# arduino.net
KiCad netlist of a schematic drawn in EAGLE
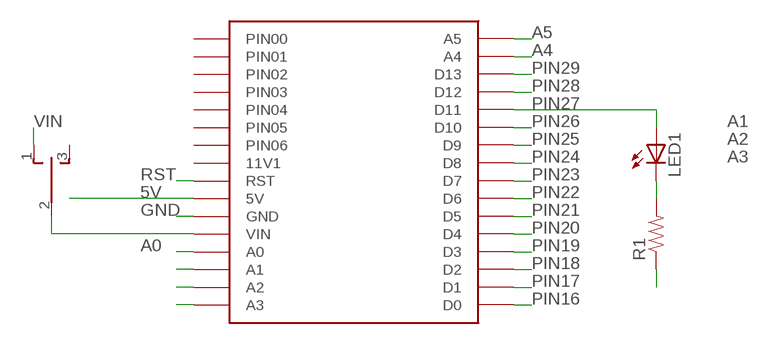
[diagram p0: schematic, sheet 1]
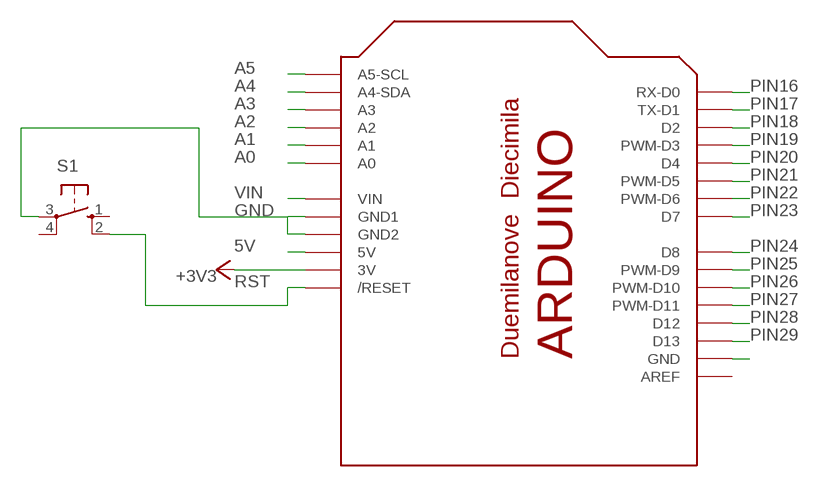
[diagram p1: schematic, sheet 2]
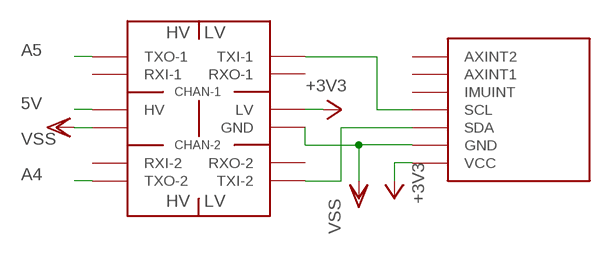
[diagram p2: schematic, sheet 3]

(export (version "E")
  (design (tool "Eeschema 10.0.6"))
  (components
    (comp (ref "S1")
      (value "10-XX")
      (footprint "eagle-import:B3F-10XX")
      (fields (field (name "MPN") "B3F-1000"))
      (libsource (lib "eagle-import") (part "10-XX"))
    )
    (comp (ref "U$6")
      (value "ARDUINO-NOHOLE")
      (footprint "eagle-import:ARDUINO-NOHOLE")
      (libsource (lib "eagle-import") (part "ARDUINO-NOHOLE"))
    )
    (comp (ref "LED1")
      (value "LED3MM")
      (footprint "eagle-import:LED3MM")
      (libsource (lib "eagle-import") (part "LED3MM"))
    )
    (comp (ref "R1")
      (value "RESISTORKIT")
      (footprint "eagle-import:AXIAL-0.3-KIT")
      (libsource (lib "eagle-import") (part "RESISTORKIT"))
    )
    (comp (ref "S2")
      (value "TL39YOSWITCH_2_ESTADOS")
      (footprint "eagle-import:TL3XYO")
      (libsource (lib "eagle-import") (part "TL39YOSWITCH_2_ESTADOS"))
    )
    (comp (ref "U$1")
      (value "BASE-FINAL")
      (footprint "eagle-import:BASE-FINAL")
      (libsource (lib "eagle-import") (part "BASE-FINAL"))
    )
    (comp (ref "U$7")
      (value "IMU3000COMBO")
      (footprint "eagle-import:IMU3000-COMBO")
      (libsource (lib "eagle-import") (part "IMU3000COMBO"))
    )
    (comp (ref "U$8")
      (value "LOGIC-LEVEL-CONVERTER")
      (footprint "eagle-import:LEVEL-CONVERTER")
      (libsource (lib "eagle-import") (part "LOGIC-LEVEL-CONVERTER"))
    )
  )
  (nets
    (net (code "1") (name "+3V3") (class "Default")
      (node (ref "U$6") (pin "3V") (pinfunction "3V_3V") (pintype "power_in"))
      (node (ref "U$7") (pin "3V3") (pinfunction "VCC_3V3") (pintype "power_in"))
      (node (ref "U$8") (pin "P$3") (pinfunction "LV_P$3") (pintype "power_in"))
    )
    (net (code "2") (name "5V") (class "Default")
      (node (ref "U$1") (pin "5V") (pinfunction "5V_5V") (pintype "bidirectional"))
      (node (ref "U$6") (pin "5V") (pinfunction "5V_5V") (pintype "power_in"))
      (node (ref "U$8") (pin "P$10") (pinfunction "HV_P$10") (pintype "power_in"))
    )
    (net (code "3") (name "A0") (class "Default")
      (node (ref "U$1") (pin "A0") (pinfunction "A0_A0") (pintype "bidirectional"))
      (node (ref "U$6") (pin "A0") (pinfunction "A0_A0") (pintype "bidirectional"))
    )
    (net (code "4") (name "A1") (class "Default")
      (node (ref "U$1") (pin "A1") (pinfunction "A1_A1") (pintype "bidirectional"))
      (node (ref "U$6") (pin "A1") (pinfunction "A1_A1") (pintype "bidirectional"))
    )
    (net (code "5") (name "A2") (class "Default")
      (node (ref "U$1") (pin "A2") (pinfunction "A2_A2") (pintype "bidirectional"))
      (node (ref "U$6") (pin "A2") (pinfunction "A2_A2") (pintype "bidirectional"))
    )
    (net (code "6") (name "A3") (class "Default")
      (node (ref "U$1") (pin "A3") (pinfunction "A3_A3") (pintype "bidirectional"))
      (node (ref "U$6") (pin "A3") (pinfunction "A3_A3") (pintype "bidirectional"))
    )
    (net (code "7") (name "A4") (class "Default")
      (node (ref "U$1") (pin "A4") (pinfunction "A4_A4") (pintype "bidirectional"))
      (node (ref "U$6") (pin "A4") (pinfunction "A4-SDA_A4") (pintype "bidirectional"))
      (node (ref "U$8") (pin "P$7") (pinfunction "TXO-2_P$7") (pintype "bidirectional"))
    )
    (net (code "8") (name "A5") (class "Default")
      (node (ref "U$1") (pin "A5") (pinfunction "A5_A5") (pintype "bidirectional"))
      (node (ref "U$6") (pin "A5") (pinfunction "A5-SCL_A5") (pintype "bidirectional"))
      (node (ref "U$8") (pin "P$12") (pinfunction "TXO-1_P$12") (pintype "bidirectional"))
    )
    (net (code "9") (name "GND") (class "Default")
      (node (ref "R1") (pin "P$1") (pinfunction "1_P$1") (pintype "passive"))
      (node (ref "S1") (pin "3") (pinfunction "P_3") (pintype "passive"))
      (node (ref "U$1") (pin "GND") (pinfunction "GND_GND") (pintype "bidirectional"))
      (node (ref "U$6") (pin "GND") (pinfunction "GND_GND") (pintype "power_in"))
      (node (ref "U$6") (pin "GND1") (pinfunction "GND1_GND1") (pintype "power_in"))
      (node (ref "U$6") (pin "GND2") (pinfunction "GND2_GND2") (pintype "power_in"))
      (node (ref "U$7") (pin "VSS") (pinfunction "GND_VSS") (pintype "power_in"))
      (node (ref "U$8") (pin "P$4") (pinfunction "GND_P$4") (pintype "power_in"))
      (node (ref "U$8") (pin "P$9") (pintype "power_in"))
    )
    (net (code "10") (name "Net-(LED1-C)") (class "Default")
      (node (ref "LED1") (pin "K") (pinfunction "C_K") (pintype "passive"))
      (node (ref "R1") (pin "P$2") (pinfunction "2_P$2") (pintype "passive"))
    )
    (net (code "11") (name "Net-(S2-P)") (class "Default")
      (node (ref "S2") (pin "2") (pinfunction "P_2") (pintype "passive"))
      (node (ref "U$1") (pin "VIN") (pinfunction "VIN_VIN") (pintype "bidirectional"))
    )
    (net (code "12") (name "Net-(U$8-TXI-1)") (class "Default")
      (node (ref "U$7") (pin "SCL") (pinfunction "SCL_SCL") (pintype "bidirectional"))
      (node (ref "U$8") (pin "P$1") (pinfunction "TXI-1_P$1") (pintype "bidirectional"))
    )
    (net (code "13") (name "Net-(U$8-TXI-2)") (class "Default")
      (node (ref "U$7") (pin "SDA") (pinfunction "SDA_SDA") (pintype "bidirectional"))
      (node (ref "U$8") (pin "P$6") (pinfunction "TXI-2_P$6") (pintype "bidirectional"))
    )
    (net (code "14") (name "PIN16") (class "Default")
      (node (ref "U$1") (pin "0") (pinfunction "D0_0") (pintype "bidirectional"))
      (node (ref "U$6") (pin "D0") (pinfunction "RX-D0_D0") (pintype "bidirectional"))
    )
    (net (code "15") (name "PIN17") (class "Default")
      (node (ref "U$1") (pin "1") (pinfunction "D1_1") (pintype "bidirectional"))
      (node (ref "U$6") (pin "D1") (pinfunction "TX-D1_D1") (pintype "bidirectional"))
    )
    (net (code "16") (name "PIN18") (class "Default")
      (node (ref "U$1") (pin "2") (pinfunction "D2_2") (pintype "bidirectional"))
      (node (ref "U$6") (pin "D2") (pinfunction "D2_D2") (pintype "bidirectional"))
    )
    (net (code "17") (name "PIN19") (class "Default")
      (node (ref "U$1") (pin "3") (pinfunction "D3_3") (pintype "bidirectional"))
      (node (ref "U$6") (pin "D3") (pinfunction "PWM-D3_D3") (pintype "bidirectional"))
    )
    (net (code "18") (name "PIN20") (class "Default")
      (node (ref "U$1") (pin "4") (pinfunction "D4_4") (pintype "bidirectional"))
      (node (ref "U$6") (pin "D4") (pinfunction "D4_D4") (pintype "bidirectional"))
    )
    (net (code "19") (name "PIN21") (class "Default")
      (node (ref "U$1") (pin "5") (pinfunction "D5_5") (pintype "bidirectional"))
      (node (ref "U$6") (pin "D5") (pinfunction "PWM-D5_D5") (pintype "bidirectional"))
    )
    (net (code "20") (name "PIN22") (class "Default")
      (node (ref "U$1") (pin "6") (pinfunction "D6_6") (pintype "bidirectional"))
      (node (ref "U$6") (pin "D6") (pinfunction "PWM-D6_D6") (pintype "bidirectional"))
    )
    (net (code "21") (name "PIN23") (class "Default")
      (node (ref "U$1") (pin "7") (pinfunction "D7_7") (pintype "bidirectional"))
      (node (ref "U$6") (pin "D7") (pinfunction "D7_D7") (pintype "bidirectional"))
    )
    (net (code "22") (name "PIN24") (class "Default")
      (node (ref "U$1") (pin "8") (pinfunction "D8_8") (pintype "bidirectional"))
      (node (ref "U$6") (pin "D8") (pinfunction "D8_D8") (pintype "bidirectional"))
    )
    (net (code "23") (name "PIN25") (class "Default")
      (node (ref "U$1") (pin "9") (pinfunction "D9_9") (pintype "bidirectional"))
      (node (ref "U$6") (pin "D9") (pinfunction "PWM-D9_D9") (pintype "bidirectional"))
    )
    (net (code "24") (name "PIN26") (class "Default")
      (node (ref "U$1") (pin "10") (pinfunction "D10_10") (pintype "bidirectional"))
      (node (ref "U$6") (pin "D10") (pinfunction "PWM-D10_D10") (pintype "bidirectional"))
    )
    (net (code "25") (name "PIN27") (class "Default")
      (node (ref "LED1") (pin "A") (pinfunction "A_A") (pintype "passive"))
      (node (ref "U$1") (pin "11") (pinfunction "D11_11") (pintype "bidirectional"))
      (node (ref "U$6") (pin "D11") (pinfunction "PWM-D11_D11") (pintype "bidirectional"))
    )
    (net (code "26") (name "PIN28") (class "Default")
      (node (ref "U$1") (pin "12") (pinfunction "D12_12") (pintype "bidirectional"))
      (node (ref "U$6") (pin "D12") (pinfunction "D12_D12") (pintype "bidirectional"))
    )
    (net (code "27") (name "PIN29") (class "Default")
      (node (ref "U$1") (pin "13") (pinfunction "D13_13") (pintype "bidirectional"))
      (node (ref "U$6") (pin "D13") (pinfunction "D13_D13") (pintype "bidirectional"))
    )
    (net (code "28") (name "RST") (class "Default")
      (node (ref "S1") (pin "2") (pinfunction "S1_2") (pintype "passive"))
      (node (ref "U$1") (pin "RST") (pinfunction "RST_RST") (pintype "bidirectional"))
      (node (ref "U$6") (pin "RESET") (pinfunction "/RESET_RESET") (pintype "bidirectional"))
    )
    (net (code "29") (name "VIN") (class "Default")
      (node (ref "S2") (pin "1") (pinfunction "O_1") (pintype "passive"))
      (node (ref "U$6") (pin "VIN") (pinfunction "VIN_VIN") (pintype "power_in"))
    )
    (net (code "30") (name "unconnected-(S1-P1-Pad4)") (class "Default")
      (node (ref "S1") (pin "4") (pinfunction "P1_4") (pintype "passive"))
    )
    (net (code "31") (name "unconnected-(S1-S-Pad1)") (class "Default")
      (node (ref "S1") (pin "1") (pinfunction "S_1") (pintype "passive"))
    )
    (net (code "32") (name "unconnected-(S2-S-Pad3)") (class "Default")
      (node (ref "S2") (pin "3") (pinfunction "S_3") (pintype "passive"))
    )
    (net (code "33") (name "unconnected-(U$1-11V1-Pad12V)") (class "Default")
      (node (ref "U$1") (pin "12V") (pinfunction "11V1_12V") (pintype "bidirectional"))
    )
    (net (code "34") (name "unconnected-(U$1-PadPIN00)") (class "Default")
      (node (ref "U$1") (pin "PIN00") (pinfunction "PIN00_PIN00") (pintype "bidirectional"))
    )
    (net (code "35") (name "unconnected-(U$1-PadPIN01)") (class "Default")
      (node (ref "U$1") (pin "PIN01") (pinfunction "PIN01_PIN01") (pintype "bidirectional"))
    )
    (net (code "36") (name "unconnected-(U$1-PadPIN02)") (class "Default")
      (node (ref "U$1") (pin "PIN02") (pinfunction "PIN02_PIN02") (pintype "bidirectional"))
    )
    (net (code "37") (name "unconnected-(U$1-PadPIN03)") (class "Default")
      (node (ref "U$1") (pin "PIN03") (pinfunction "PIN03_PIN03") (pintype "bidirectional"))
    )
    (net (code "38") (name "unconnected-(U$1-PadPIN04)") (class "Default")
      (node (ref "U$1") (pin "PIN04") (pinfunction "PIN04_PIN04") (pintype "bidirectional"))
    )
    (net (code "39") (name "unconnected-(U$1-PadPIN05)") (class "Default")
      (node (ref "U$1") (pin "PIN05") (pinfunction "PIN05_PIN05") (pintype "bidirectional"))
    )
    (net (code "40") (name "unconnected-(U$1-PadPIN06)") (class "Default")
      (node (ref "U$1") (pin "PIN06") (pinfunction "PIN06_PIN06") (pintype "bidirectional"))
    )
    (net (code "41") (name "unconnected-(U$6-PadAREF)") (class "Default")
      (node (ref "U$6") (pin "AREF") (pinfunction "AREF_AREF") (pintype "bidirectional"))
    )
    (net (code "42") (name "unconnected-(U$7-PadAXINT1)") (class "Default")
      (node (ref "U$7") (pin "AXINT1") (pinfunction "AXINT1_AXINT1") (pintype "bidirectional"))
    )
    (net (code "43") (name "unconnected-(U$7-PadAXINT2)") (class "Default")
      (node (ref "U$7") (pin "AXINT2") (pinfunction "AXINT2_AXINT2") (pintype "bidirectional"))
    )
    (net (code "44") (name "unconnected-(U$7-PadIMUINT)") (class "Default")
      (node (ref "U$7") (pin "IMUINT") (pinfunction "IMUINT_IMUINT") (pintype "bidirectional"))
    )
    (net (code "45") (name "unconnected-(U$8-RXI-1-PadP$11)") (class "Default")
      (node (ref "U$8") (pin "P$11") (pinfunction "RXI-1_P$11") (pintype "bidirectional"))
    )
    (net (code "46") (name "unconnected-(U$8-RXI-2-PadP$8)") (class "Default")
      (node (ref "U$8") (pin "P$8") (pinfunction "RXI-2_P$8") (pintype "bidirectional"))
    )
    (net (code "47") (name "unconnected-(U$8-RXO-1-PadP$2)") (class "Default")
      (node (ref "U$8") (pin "P$2") (pinfunction "RXO-1_P$2") (pintype "bidirectional"))
    )
    (net (code "48") (name "unconnected-(U$8-RXO-2-PadP$5)") (class "Default")
      (node (ref "U$8") (pin "P$5") (pinfunction "RXO-2_P$5") (pintype "bidirectional"))
    )
  )
)
